# smalltest.net
KiCad netlist of a schematic drawn in EAGLE
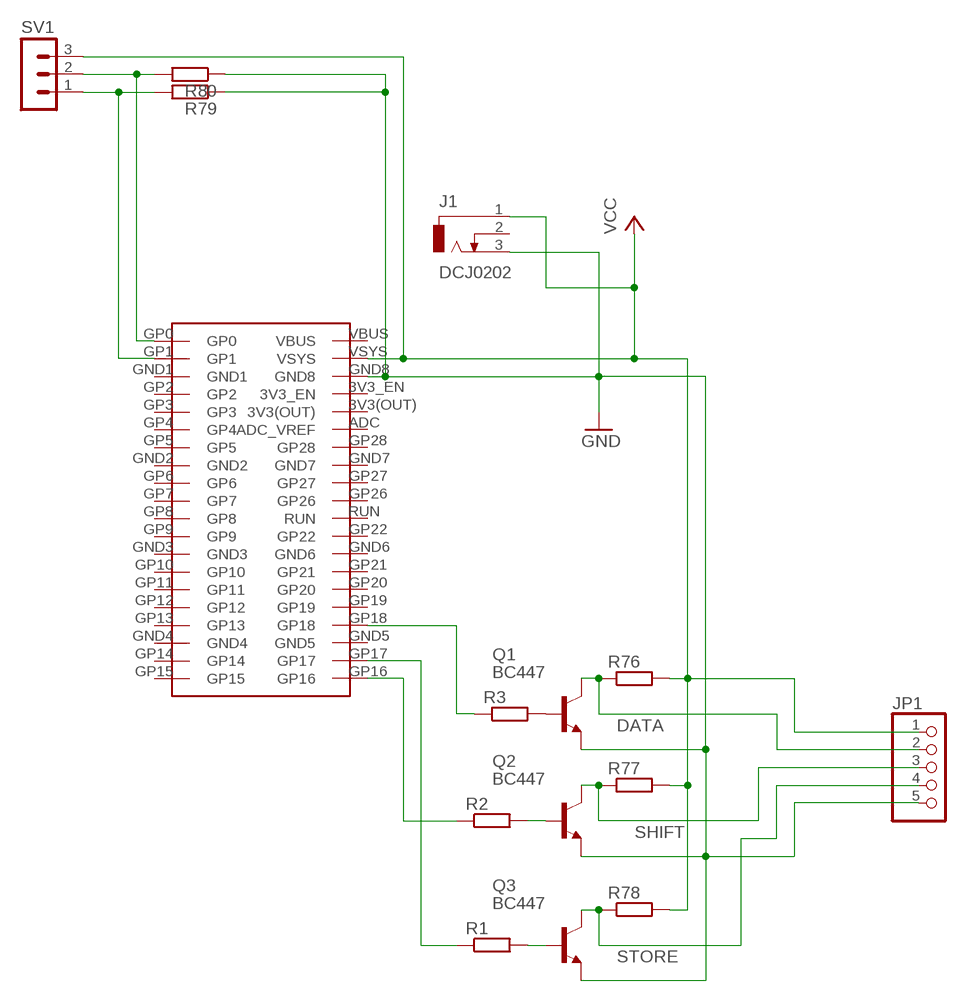
[diagram p0: schematic, sheet 1]

(export (version "E")
  (design (tool "Eeschema 10.0.6"))
  (components
    (comp (ref "J1")
      (value "DCJ0202")
      (footprint "eagle-import:DCJ0202")
      (libsource (lib "eagle-import") (part "DCJ0202"))
    )
    (comp (ref "JP1")
      (value "PINHD-1X5")
      (footprint "eagle-import:1X05")
      (libsource (lib "eagle-import") (part "PINHD-1X5"))
    )
    (comp (ref "Q1")
      (value "BC447")
      (footprint "eagle-import:TO92-EBC")
      (libsource (lib "eagle-import") (part "BC447"))
    )
    (comp (ref "Q2")
      (value "BC447")
      (footprint "eagle-import:TO92-EBC")
      (libsource (lib "eagle-import") (part "BC447"))
    )
    (comp (ref "Q3")
      (value "BC447")
      (footprint "eagle-import:TO92-EBC")
      (libsource (lib "eagle-import") (part "BC447"))
    )
    (comp (ref "R1")
      (value "R-EU_0207/10")
      (footprint "eagle-import:0207_10")
      (libsource (lib "eagle-import") (part "R-EU_0207/10"))
    )
    (comp (ref "R2")
      (value "R-EU_0207/10")
      (footprint "eagle-import:0207_10")
      (libsource (lib "eagle-import") (part "R-EU_0207/10"))
    )
    (comp (ref "R3")
      (value "R-EU_0207/10")
      (footprint "eagle-import:0207_10")
      (libsource (lib "eagle-import") (part "R-EU_0207/10"))
    )
    (comp (ref "R76")
      (value "R-EU_0207/10")
      (footprint "eagle-import:0207_10")
      (libsource (lib "eagle-import") (part "R-EU_0207/10"))
    )
    (comp (ref "R77")
      (value "R-EU_0207/10")
      (footprint "eagle-import:0207_10")
      (libsource (lib "eagle-import") (part "R-EU_0207/10"))
    )
    (comp (ref "R78")
      (value "R-EU_0207/10")
      (footprint "eagle-import:0207_10")
      (libsource (lib "eagle-import") (part "R-EU_0207/10"))
    )
    (comp (ref "R79")
      (value "R-EU_0207/10")
      (footprint "eagle-import:0207_10")
      (libsource (lib "eagle-import") (part "R-EU_0207/10"))
    )
    (comp (ref "R80")
      (value "R-EU_0207/10")
      (footprint "eagle-import:0207_10")
      (libsource (lib "eagle-import") (part "R-EU_0207/10"))
    )
    (comp (ref "SV1")
      (value "MA03-1")
      (footprint "eagle-import:MA03-1")
      (libsource (lib "eagle-import") (part "MA03-1"))
    )
    (comp (ref "U$2")
      (value "PI_PICO")
      (footprint "eagle-import:PI_PICO")
      (libsource (lib "eagle-import") (part "PI_PICO"))
    )
  )
  (nets
    (net (code "1") (name "/DATA") (class "Default")
      (node (ref "JP1") (pin "2") (pinfunction "2_2") (pintype "passive"))
      (node (ref "Q1") (pin "C") (pinfunction "C_C") (pintype "passive"))
      (node (ref "R76") (pin "1") (pinfunction "1_1") (pintype "passive"))
    )
    (net (code "2") (name "/SHIFT") (class "Default")
      (node (ref "JP1") (pin "3") (pinfunction "3_3") (pintype "passive"))
      (node (ref "Q2") (pin "C") (pinfunction "C_C") (pintype "passive"))
      (node (ref "R77") (pin "1") (pinfunction "1_1") (pintype "passive"))
    )
    (net (code "3") (name "/STORE") (class "Default")
      (node (ref "JP1") (pin "4") (pinfunction "4_4") (pintype "passive"))
      (node (ref "Q3") (pin "C") (pinfunction "C_C") (pintype "passive"))
      (node (ref "R78") (pin "1") (pinfunction "1_1") (pintype "passive"))
    )
    (net (code "4") (name "GND") (class "Default")
      (node (ref "J1") (pin "3") (pinfunction "3_3") (pintype "passive"))
      (node (ref "JP1") (pin "5") (pinfunction "5_5") (pintype "passive"))
      (node (ref "Q1") (pin "E") (pinfunction "E_E") (pintype "passive"))
      (node (ref "Q2") (pin "E") (pinfunction "E_E") (pintype "passive"))
      (node (ref "Q3") (pin "E") (pinfunction "E_E") (pintype "passive"))
      (node (ref "R79") (pin "1") (pinfunction "1_1") (pintype "passive"))
      (node (ref "R80") (pin "1") (pinfunction "1_1") (pintype "passive"))
      (node (ref "U$2") (pin "GND8") (pinfunction "GND8_GND8") (pintype "bidirectional"))
    )
    (net (code "5") (name "Net-(Q1-PadB)") (class "Default")
      (node (ref "Q1") (pin "B") (pinfunction "B_B") (pintype "passive"))
      (node (ref "R3") (pin "2") (pinfunction "2_2") (pintype "passive"))
    )
    (net (code "6") (name "Net-(Q2-PadB)") (class "Default")
      (node (ref "Q2") (pin "B") (pinfunction "B_B") (pintype "passive"))
      (node (ref "R2") (pin "2") (pinfunction "2_2") (pintype "passive"))
    )
    (net (code "7") (name "Net-(Q3-PadB)") (class "Default")
      (node (ref "Q3") (pin "B") (pinfunction "B_B") (pintype "passive"))
      (node (ref "R1") (pin "2") (pinfunction "2_2") (pintype "passive"))
    )
    (net (code "8") (name "Net-(R1-Pad1)") (class "Default")
      (node (ref "R1") (pin "1") (pinfunction "1_1") (pintype "passive"))
      (node (ref "U$2") (pin "GP17") (pinfunction "GP17_GP17") (pintype "bidirectional"))
    )
    (net (code "9") (name "Net-(R2-Pad1)") (class "Default")
      (node (ref "R2") (pin "1") (pinfunction "1_1") (pintype "passive"))
      (node (ref "U$2") (pin "GP16") (pinfunction "GP16_GP16") (pintype "bidirectional"))
    )
    (net (code "10") (name "Net-(R3-Pad1)") (class "Default")
      (node (ref "R3") (pin "1") (pinfunction "1_1") (pintype "passive"))
      (node (ref "U$2") (pin "GP18") (pinfunction "GP18_GP18") (pintype "bidirectional"))
    )
    (net (code "11") (name "Net-(R79-Pad2)") (class "Default")
      (node (ref "R79") (pin "2") (pinfunction "2_2") (pintype "passive"))
      (node (ref "SV1") (pin "1") (pinfunction "1_1") (pintype "passive"))
      (node (ref "U$2") (pin "GP1") (pinfunction "GP1_GP1") (pintype "bidirectional"))
    )
    (net (code "12") (name "Net-(R80-Pad2)") (class "Default")
      (node (ref "R80") (pin "2") (pinfunction "2_2") (pintype "passive"))
      (node (ref "SV1") (pin "2") (pinfunction "2_2") (pintype "passive"))
      (node (ref "U$2") (pin "GP0") (pinfunction "GP0_GP0") (pintype "bidirectional"))
    )
    (net (code "13") (name "VCC") (class "Default")
      (node (ref "J1") (pin "1") (pinfunction "1_1") (pintype "passive"))
      (node (ref "JP1") (pin "1") (pinfunction "1_1") (pintype "passive"))
      (node (ref "R76") (pin "2") (pinfunction "2_2") (pintype "passive"))
      (node (ref "R77") (pin "2") (pinfunction "2_2") (pintype "passive"))
      (node (ref "R78") (pin "2") (pinfunction "2_2") (pintype "passive"))
      (node (ref "SV1") (pin "3") (pinfunction "3_3") (pintype "passive"))
      (node (ref "U$2") (pin "VSYS") (pinfunction "VSYS_VSYS") (pintype "bidirectional"))
    )
    (net (code "14") (name "unconnected-(J1-Pad2)") (class "Default")
      (node (ref "J1") (pin "2") (pinfunction "2_2") (pintype "passive"))
    )
    (net (code "15") (name "unconnected-(U$2-ADC_VREF-PadADC)") (class "Default")
      (node (ref "U$2") (pin "ADC") (pinfunction "ADC_VREF_ADC") (pintype "bidirectional"))
    )
    (net (code "16") (name "unconnected-(U$2-Pad3V3(OUT))") (class "Default")
      (node (ref "U$2") (pin "3V3(OUT)") (pinfunction "3V3(OUT)_3V3(OUT)") (pintype "bidirectional"))
    )
    (net (code "17") (name "unconnected-(U$2-Pad3V3_EN)") (class "Default")
      (node (ref "U$2") (pin "3V3_EN") (pinfunction "3V3_EN_3V3_EN") (pintype "bidirectional"))
    )
    (net (code "18") (name "unconnected-(U$2-PadGND1)") (class "Default")
      (node (ref "U$2") (pin "GND1") (pinfunction "GND1_GND1") (pintype "bidirectional"))
    )
    (net (code "19") (name "unconnected-(U$2-PadGND2)") (class "Default")
      (node (ref "U$2") (pin "GND2") (pinfunction "GND2_GND2") (pintype "bidirectional"))
    )
    (net (code "20") (name "unconnected-(U$2-PadGND3)") (class "Default")
      (node (ref "U$2") (pin "GND3") (pinfunction "GND3_GND3") (pintype "bidirectional"))
    )
    (net (code "21") (name "unconnected-(U$2-PadGND4)") (class "Default")
      (node (ref "U$2") (pin "GND4") (pinfunction "GND4_GND4") (pintype "bidirectional"))
    )
    (net (code "22") (name "unconnected-(U$2-PadGND5)") (class "Default")
      (node (ref "U$2") (pin "GND5") (pinfunction "GND5_GND5") (pintype "bidirectional"))
    )
    (net (code "23") (name "unconnected-(U$2-PadGND6)") (class "Default")
      (node (ref "U$2") (pin "GND6") (pinfunction "GND6_GND6") (pintype "bidirectional"))
    )
    (net (code "24") (name "unconnected-(U$2-PadGND7)") (class "Default")
      (node (ref "U$2") (pin "GND7") (pinfunction "GND7_GND7") (pintype "bidirectional"))
    )
    (net (code "25") (name "unconnected-(U$2-PadGP2)") (class "Default")
      (node (ref "U$2") (pin "GP2") (pinfunction "GP2_GP2") (pintype "bidirectional"))
    )
    (net (code "26") (name "unconnected-(U$2-PadGP3)") (class "Default")
      (node (ref "U$2") (pin "GP3") (pinfunction "GP3_GP3") (pintype "bidirectional"))
    )
    (net (code "27") (name "unconnected-(U$2-PadGP4)") (class "Default")
      (node (ref "U$2") (pin "GP4") (pinfunction "GP4_GP4") (pintype "bidirectional"))
    )
    (net (code "28") (name "unconnected-(U$2-PadGP5)") (class "Default")
      (node (ref "U$2") (pin "GP5") (pinfunction "GP5_GP5") (pintype "bidirectional"))
    )
    (net (code "29") (name "unconnected-(U$2-PadGP6)") (class "Default")
      (node (ref "U$2") (pin "GP6") (pinfunction "GP6_GP6") (pintype "bidirectional"))
    )
    (net (code "30") (name "unconnected-(U$2-PadGP7)") (class "Default")
      (node (ref "U$2") (pin "GP7") (pinfunction "GP7_GP7") (pintype "bidirectional"))
    )
    (net (code "31") (name "unconnected-(U$2-PadGP8)") (class "Default")
      (node (ref "U$2") (pin "GP8") (pinfunction "GP8_GP8") (pintype "bidirectional"))
    )
    (net (code "32") (name "unconnected-(U$2-PadGP9)") (class "Default")
      (node (ref "U$2") (pin "GP9") (pinfunction "GP9_GP9") (pintype "bidirectional"))
    )
    (net (code "33") (name "unconnected-(U$2-PadGP10)") (class "Default")
      (node (ref "U$2") (pin "GP10") (pinfunction "GP10_GP10") (pintype "bidirectional"))
    )
    (net (code "34") (name "unconnected-(U$2-PadGP11)") (class "Default")
      (node (ref "U$2") (pin "GP11") (pinfunction "GP11_GP11") (pintype "bidirectional"))
    )
    (net (code "35") (name "unconnected-(U$2-PadGP12)") (class "Default")
      (node (ref "U$2") (pin "GP12") (pinfunction "GP12_GP12") (pintype "bidirectional"))
    )
    (net (code "36") (name "unconnected-(U$2-PadGP13)") (class "Default")
      (node (ref "U$2") (pin "GP13") (pinfunction "GP13_GP13") (pintype "bidirectional"))
    )
    (net (code "37") (name "unconnected-(U$2-PadGP14)") (class "Default")
      (node (ref "U$2") (pin "GP14") (pinfunction "GP14_GP14") (pintype "bidirectional"))
    )
    (net (code "38") (name "unconnected-(U$2-PadGP15)") (class "Default")
      (node (ref "U$2") (pin "GP15") (pinfunction "GP15_GP15") (pintype "bidirectional"))
    )
    (net (code "39") (name "unconnected-(U$2-PadGP19)") (class "Default")
      (node (ref "U$2") (pin "GP19") (pinfunction "GP19_GP19") (pintype "bidirectional"))
    )
    (net (code "40") (name "unconnected-(U$2-PadGP20)") (class "Default")
      (node (ref "U$2") (pin "GP20") (pinfunction "GP20_GP20") (pintype "bidirectional"))
    )
    (net (code "41") (name "unconnected-(U$2-PadGP21)") (class "Default")
      (node (ref "U$2") (pin "GP21") (pinfunction "GP21_GP21") (pintype "bidirectional"))
    )
    (net (code "42") (name "unconnected-(U$2-PadGP22)") (class "Default")
      (node (ref "U$2") (pin "GP22") (pinfunction "GP22_GP22") (pintype "bidirectional"))
    )
    (net (code "43") (name "unconnected-(U$2-PadGP26)") (class "Default")
      (node (ref "U$2") (pin "GP26") (pinfunction "GP26_GP26") (pintype "bidirectional"))
    )
    (net (code "44") (name "unconnected-(U$2-PadGP27)") (class "Default")
      (node (ref "U$2") (pin "GP27") (pinfunction "GP27_GP27") (pintype "bidirectional"))
    )
    (net (code "45") (name "unconnected-(U$2-PadGP28)") (class "Default")
      (node (ref "U$2") (pin "GP28") (pinfunction "GP28_GP28") (pintype "bidirectional"))
    )
    (net (code "46") (name "unconnected-(U$2-PadRUN)") (class "Default")
      (node (ref "U$2") (pin "RUN") (pinfunction "RUN_RUN") (pintype "bidirectional"))
    )
    (net (code "47") (name "unconnected-(U$2-PadVBUS)") (class "Default")
      (node (ref "U$2") (pin "VBUS") (pinfunction "VBUS_VBUS") (pintype "bidirectional"))
    )
  )
)
